# VESC1SC.net
KiCad netlist of a schematic drawn in Altium Designer
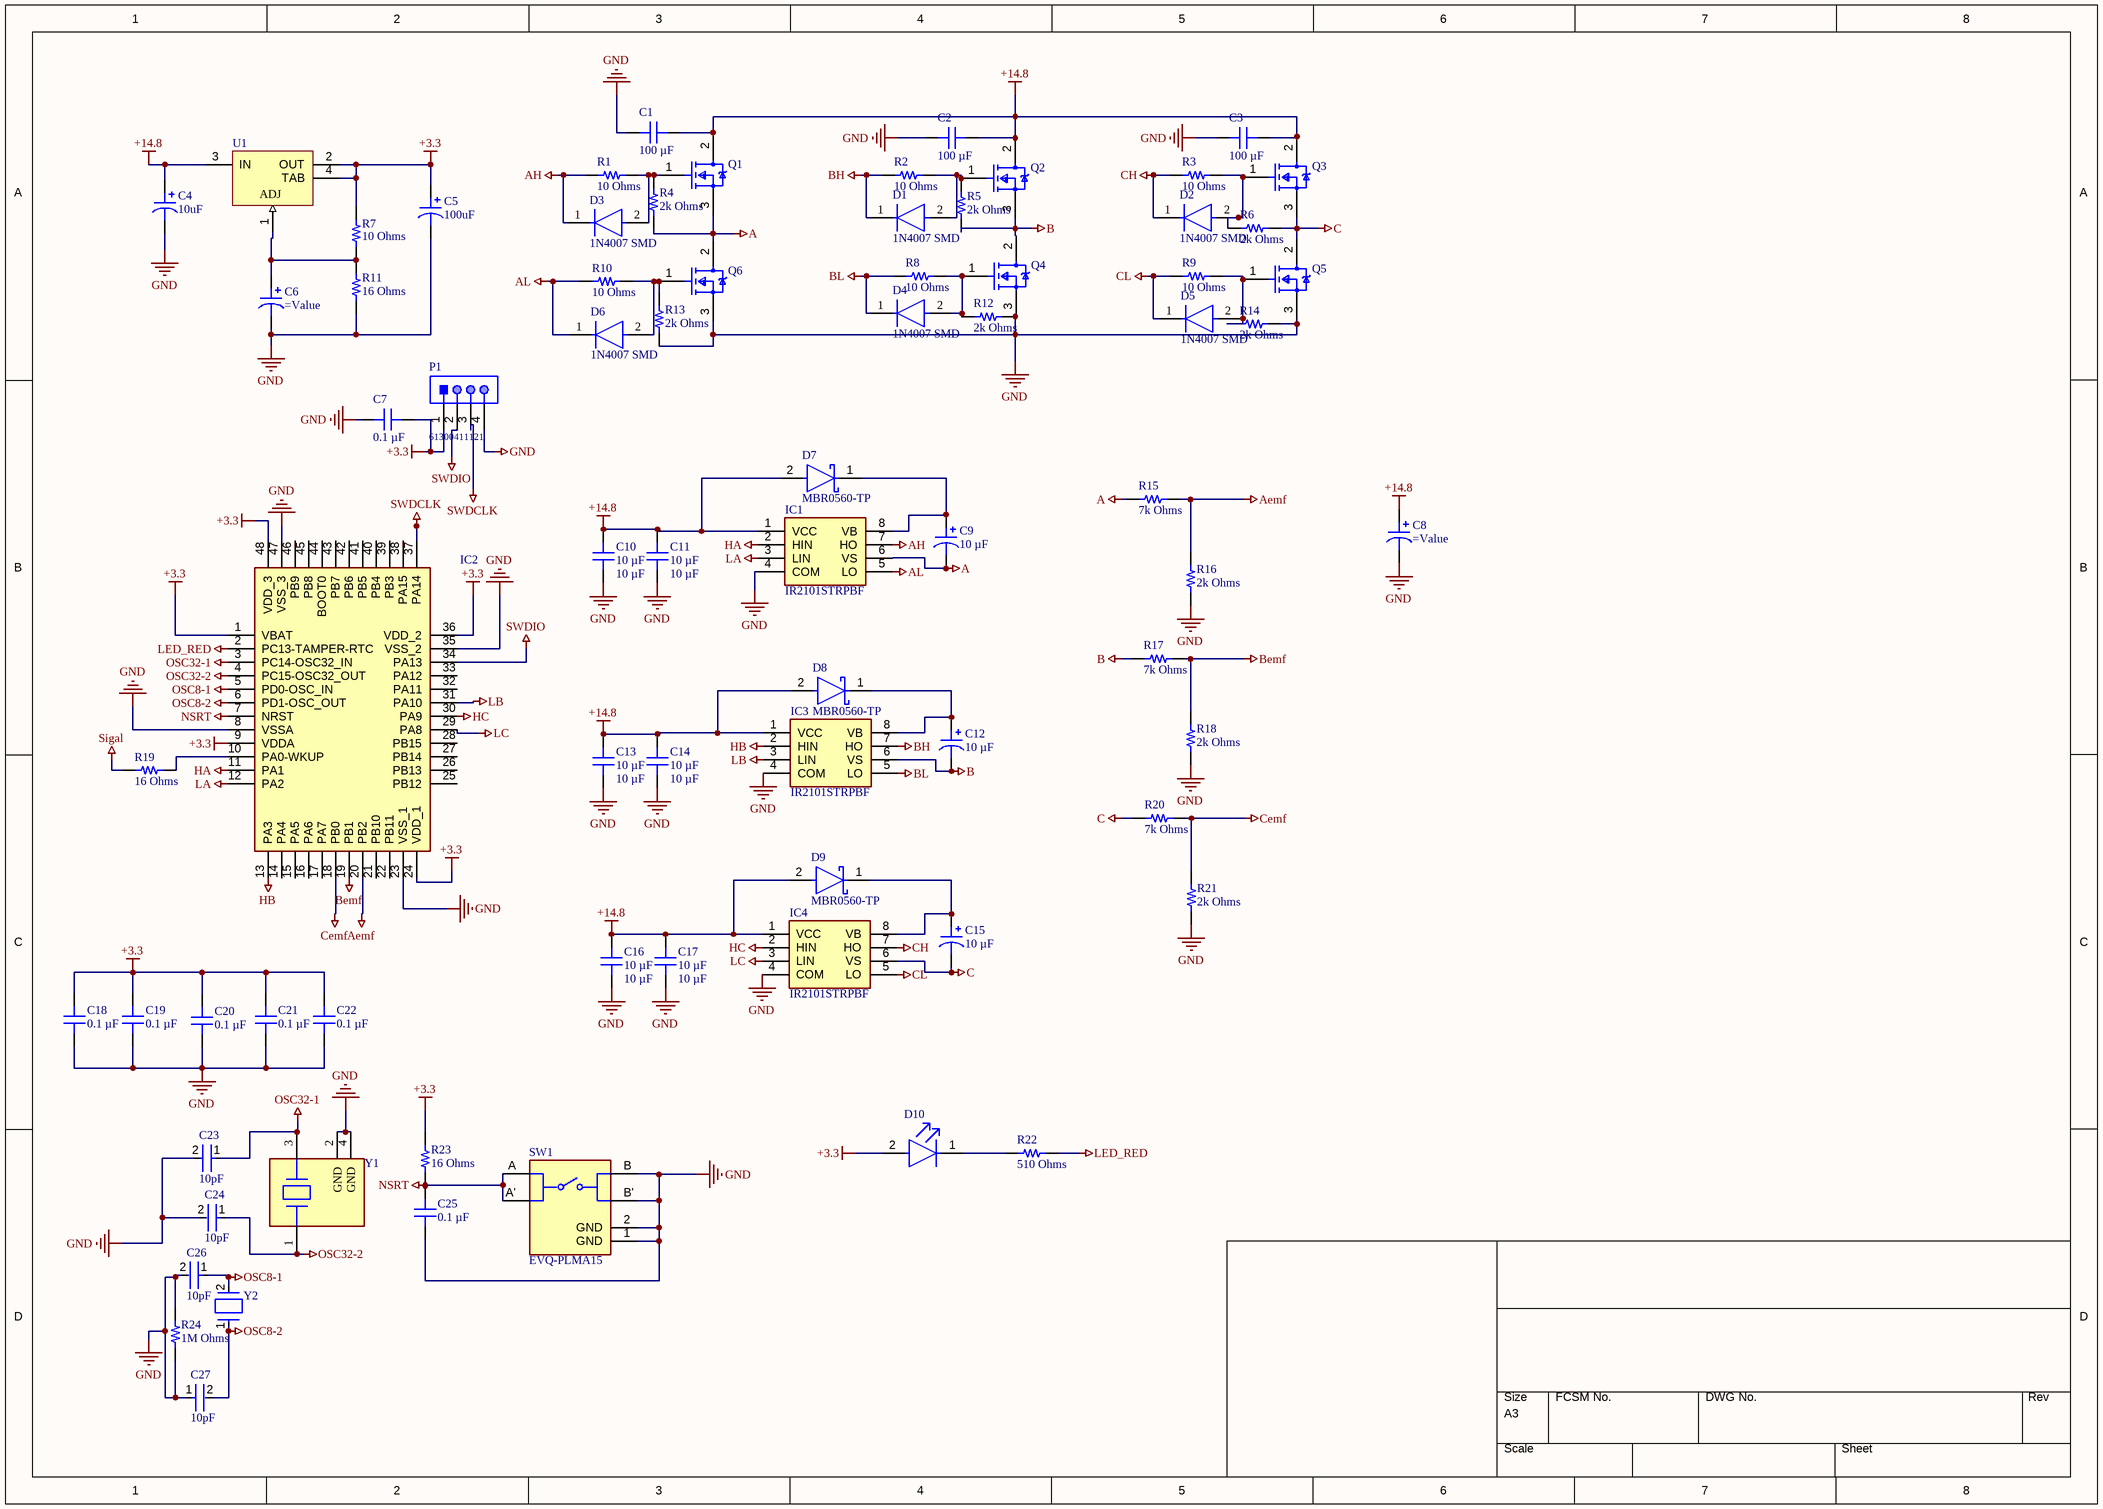
[diagram p0: VESC1SC.SchDoc]

(export (version "E")
  (design (tool "Eeschema 10.0.6"))
  (components
    (comp (ref "C1")
      (value "100 µF")
      (footprint "CAP 0805_2012")
      (description "CAP CER 100UF 2.5V X5R 0805")
      (fields (field (name "PART NUMBER") "PMK212BBJ107MG-T") (field (name "MANUFACTURER") "Taiyo Yuden"))
      (libsource (lib "Celestial Altium Library - altium_library") (part "Capacitor"))
    )
    (comp (ref "C2")
      (value "100 µF")
      (footprint "CAP 0805_2012")
      (description "CAP CER 100UF 2.5V X5R 0805")
      (fields (field (name "PART NUMBER") "PMK212BBJ107MG-T") (field (name "MANUFACTURER") "Taiyo Yuden"))
      (libsource (lib "Celestial Altium Library - altium_library") (part "Capacitor"))
    )
    (comp (ref "C3")
      (value "100 µF")
      (footprint "CAP 0805_2012")
      (description "CAP CER 100UF 2.5V X5R 0805")
      (fields (field (name "PART NUMBER") "PMK212BBJ107MG-T") (field (name "MANUFACTURER") "Taiyo Yuden"))
      (libsource (lib "Celestial Altium Library - altium_library") (part "Capacitor"))
    )
    (comp (ref "C4")
      (value "10uF")
      (footprint "CAP ALSMD 4.3MM H5.4MM")
      (description "CAP ALUM 10UF 20% 16V SMD")
      (fields (field (name "PART NUMBER") "UWX1C100MCL1GB"))
      (libsource (lib "Celestial Altium Library - altium_library") (part "Polarised Capacitor"))
    )
    (comp (ref "C5")
      (value "100uF")
      (footprint "CAP ALSMD 4.3MM H5.4MM")
      (description "CAP ALUM 10UF 20% 16V SMD")
      (fields (field (name "PART NUMBER") "UWX1C100MCL1GB"))
      (libsource (lib "Celestial Altium Library - altium_library") (part "Polarised Capacitor"))
    )
    (comp (ref "C6")
      (value "~")
      (footprint "CAP ALSMD 4.3MM H5.4MM")
      (description "CAP ALUM 10UF 20% 16V SMD")
      (fields (field (name "PART NUMBER") "UWX1C100MCL1GB"))
      (libsource (lib "Celestial Altium Library - altium_library") (part "Polarised Capacitor"))
    )
    (comp (ref "C7")
      (value "0.1 µF")
      (footprint "CAP 0805_2012")
      (description "CAP CER 0.1UF 100V X5R 0805")
      (fields (field (name "PART NUMBER") "HMK212BJ104KG-T") (field (name "MANUFACTURER") "Taiyo Yuden"))
      (libsource (lib "Celestial Altium Library - altium_library") (part "Capacitor"))
    )
    (comp (ref "C8")
      (value "~")
      (footprint "CAP TH ALUM ELEC D5.00mm S2.50mm H12.00mm")
      (description "CAP ALUM 10UF 20% 50V RADIAL")
      (fields (field (name "PART NUMBER") "ECA-1HHG100I"))
      (libsource (lib "Celestial Altium Library - altium_library") (part "Polarised Capacitor"))
    )
    (comp (ref "C9")
      (value "10 µF")
      (footprint "CAP ALSMD 4.3MM H5.4MM")
      (description "CAP ALUM 10UF 20% 16V SMD")
      (fields (field (name "PART NUMBER") "UWX1C100MCL1GB") (field (name "MANUFACTURER") "Nichicon"))
      (libsource (lib "Celestial Altium Library - altium_library") (part "Polarised Capacitor"))
    )
    (comp (ref "C10")
      (value "10 µF")
      (footprint "CAP 0805_2012")
      (description "CAP CER 10UF 16V X6S 0805")
      (fields (field (name "PART NUMBER") "C2012X6S1C106K125AC") (field (name "ALTIUM_VALUE") "10 µF"))
      (libsource (lib "Celestial Altium Library - altium_library") (part "Capacitor"))
    )
    (comp (ref "C11")
      (value "10 µF")
      (footprint "CAP 0805_2012")
      (description "CAP CER 10UF 16V X6S 0805")
      (fields (field (name "PART NUMBER") "C2012X6S1C106K125AC") (field (name "ALTIUM_VALUE") "10 µF"))
      (libsource (lib "Celestial Altium Library - altium_library") (part "Capacitor"))
    )
    (comp (ref "C12")
      (value "10 µF")
      (footprint "CAP ALSMD 4.3MM H5.4MM")
      (description "CAP ALUM 10UF 20% 16V SMD")
      (fields (field (name "PART NUMBER") "UWX1C100MCL1GB") (field (name "MANUFACTURER") "Nichicon"))
      (libsource (lib "Celestial Altium Library - altium_library") (part "Polarised Capacitor"))
    )
    (comp (ref "C13")
      (value "10 µF")
      (footprint "CAP 0805_2012")
      (description "CAP CER 10UF 16V X6S 0805")
      (fields (field (name "PART NUMBER") "C2012X6S1C106K125AC") (field (name "ALTIUM_VALUE") "10 µF"))
      (libsource (lib "Celestial Altium Library - altium_library") (part "Capacitor"))
    )
    (comp (ref "C14")
      (value "10 µF")
      (footprint "CAP 0805_2012")
      (description "CAP CER 10UF 16V X6S 0805")
      (fields (field (name "PART NUMBER") "C2012X6S1C106K125AC") (field (name "ALTIUM_VALUE") "10 µF"))
      (libsource (lib "Celestial Altium Library - altium_library") (part "Capacitor"))
    )
    (comp (ref "C15")
      (value "10 µF")
      (footprint "CAP ALSMD 4.3MM H5.4MM")
      (description "CAP ALUM 10UF 20% 16V SMD")
      (fields (field (name "PART NUMBER") "UWX1C100MCL1GB") (field (name "MANUFACTURER") "Nichicon"))
      (libsource (lib "Celestial Altium Library - altium_library") (part "Polarised Capacitor"))
    )
    (comp (ref "C16")
      (value "10 µF")
      (footprint "CAP 0805_2012")
      (description "CAP CER 10UF 16V X6S 0805")
      (fields (field (name "PART NUMBER") "C2012X6S1C106K125AC") (field (name "ALTIUM_VALUE") "10 µF"))
      (libsource (lib "Celestial Altium Library - altium_library") (part "Capacitor"))
    )
    (comp (ref "C17")
      (value "10 µF")
      (footprint "CAP 0805_2012")
      (description "CAP CER 10UF 16V X6S 0805")
      (fields (field (name "PART NUMBER") "C2012X6S1C106K125AC") (field (name "ALTIUM_VALUE") "10 µF"))
      (libsource (lib "Celestial Altium Library - altium_library") (part "Capacitor"))
    )
    (comp (ref "C18")
      (value "0.1 µF")
      (footprint "CAP 0805_2012")
      (description "CAP CER 0.1UF 100V X5R 0805")
      (fields (field (name "PART NUMBER") "HMK212BJ104KG-T") (field (name "MANUFACTURER") "Taiyo Yuden"))
      (libsource (lib "Celestial Altium Library - altium_library") (part "Capacitor"))
    )
    (comp (ref "C19")
      (value "0.1 µF")
      (footprint "CAP 0805_2012")
      (description "CAP CER 0.1UF 100V X5R 0805")
      (fields (field (name "PART NUMBER") "HMK212BJ104KG-T") (field (name "MANUFACTURER") "Taiyo Yuden"))
      (libsource (lib "Celestial Altium Library - altium_library") (part "Capacitor"))
    )
    (comp (ref "C20")
      (value "0.1 µF")
      (footprint "CAP 0805_2012")
      (description "CAP CER 0.1UF 100V X5R 0805")
      (fields (field (name "PART NUMBER") "HMK212BJ104KG-T") (field (name "MANUFACTURER") "Taiyo Yuden"))
      (libsource (lib "Celestial Altium Library - altium_library") (part "Capacitor"))
    )
    (comp (ref "C21")
      (value "0.1 µF")
      (footprint "CAP 0805_2012")
      (description "CAP CER 0.1UF 100V X5R 0805")
      (fields (field (name "PART NUMBER") "HMK212BJ104KG-T") (field (name "MANUFACTURER") "Taiyo Yuden"))
      (libsource (lib "Celestial Altium Library - altium_library") (part "Capacitor"))
    )
    (comp (ref "C22")
      (value "0.1 µF")
      (footprint "CAP 0805_2012")
      (description "CAP CER 0.1UF 100V X5R 0805")
      (fields (field (name "PART NUMBER") "HMK212BJ104KG-T") (field (name "MANUFACTURER") "Taiyo Yuden"))
      (libsource (lib "Celestial Altium Library - altium_library") (part "Capacitor"))
    )
    (comp (ref "C23")
      (value "10pF")
      (footprint "FP-C0805C-DN-MFG")
      (description "Capacitor; Ceramic; Cap 10 pF; Tol 5%; Vol-Rtg 50 VDC; SMT; 0805; COG (NPO); Tape&Reel")
      (fields
        (field (name "OCTOPART") "https://octopart.com/c0805c100j5gactu-kemet-104357")
        (field (name "MANUFACTURER PART NUMBER") "C0805C100J5GACTU")
      )
      (libsource (lib "Altium Content Vault") (part "b4654b650e69147ec39a6b967a45e02"))
    )
    (comp (ref "C24")
      (value "10pF")
      (footprint "FP-C0805C-DN-MFG")
      (description "Capacitor; Ceramic; Cap 10 pF; Tol 5%; Vol-Rtg 50 VDC; SMT; 0805; COG (NPO); Tape&Reel")
      (fields
        (field (name "OCTOPART") "https://octopart.com/c0805c100j5gactu-kemet-104357")
        (field (name "MANUFACTURER PART NUMBER") "C0805C100J5GACTU")
      )
      (libsource (lib "Altium Content Vault") (part "b4654b650e69147ec39a6b967a45e02"))
    )
    (comp (ref "C25")
      (value "0.1 µF")
      (footprint "CAP 0805_2012")
      (description "CAP CER 0.1UF 100V X5R 0805")
      (fields (field (name "PART NUMBER") "HMK212BJ104KG-T") (field (name "MANUFACTURER") "Taiyo Yuden"))
      (libsource (lib "Celestial Altium Library - altium_library") (part "Capacitor"))
    )
    (comp (ref "C26")
      (value "10pF")
      (footprint "FP-C0805C-DN-MFG")
      (description "Capacitor; Ceramic; Cap 10 pF; Tol 5%; Vol-Rtg 50 VDC; SMT; 0805; COG (NPO); Tape&Reel")
      (fields
        (field (name "OCTOPART") "https://octopart.com/c0805c100j5gactu-kemet-104357")
        (field (name "MANUFACTURER PART NUMBER") "C0805C100J5GACTU")
      )
      (libsource (lib "Altium Content Vault") (part "b4654b650e69147ec39a6b967a45e02"))
    )
    (comp (ref "C27")
      (value "10pF")
      (footprint "FP-C0805C-DN-MFG")
      (description "Capacitor; Ceramic; Cap 10 pF; Tol 5%; Vol-Rtg 50 VDC; SMT; 0805; COG (NPO); Tape&Reel")
      (fields
        (field (name "OCTOPART") "https://octopart.com/c0805c100j5gactu-kemet-104357")
        (field (name "MANUFACTURER PART NUMBER") "C0805C100J5GACTU")
      )
      (libsource (lib "Altium Content Vault") (part "b4654b650e69147ec39a6b967a45e02"))
    )
    (comp (ref "D1")
      (value "1N4007 SMD")
      (footprint "FP-1N4007_SMD-IPC_C")
      (description "Rectifier, 1Kv, 1A, Do-214Ac Rohs Compliant: Yes")
      (libsource (lib "Altium Content Vault") (part "d7152d700b627762746794eb795d46e"))
    )
    (comp (ref "D2")
      (value "1N4007 SMD")
      (footprint "FP-1N4007_SMD-IPC_C")
      (description "Rectifier, 1Kv, 1A, Do-214Ac Rohs Compliant: Yes")
      (libsource (lib "Altium Content Vault") (part "d7152d700b627762746794eb795d46e"))
    )
    (comp (ref "D3")
      (value "1N4007 SMD")
      (footprint "FP-1N4007_SMD-IPC_C")
      (description "Rectifier, 1Kv, 1A, Do-214Ac Rohs Compliant: Yes")
      (libsource (lib "Altium Content Vault") (part "d7152d700b627762746794eb795d46e"))
    )
    (comp (ref "D4")
      (value "1N4007 SMD")
      (footprint "FP-1N4007_SMD-IPC_C")
      (description "Rectifier, 1Kv, 1A, Do-214Ac Rohs Compliant: Yes")
      (libsource (lib "Altium Content Vault") (part "d7152d700b627762746794eb795d46e"))
    )
    (comp (ref "D5")
      (value "1N4007 SMD")
      (footprint "FP-1N4007_SMD-IPC_C")
      (description "Rectifier, 1Kv, 1A, Do-214Ac Rohs Compliant: Yes")
      (libsource (lib "Altium Content Vault") (part "d7152d700b627762746794eb795d46e"))
    )
    (comp (ref "D6")
      (value "1N4007 SMD")
      (footprint "FP-1N4007_SMD-IPC_C")
      (description "Rectifier, 1Kv, 1A, Do-214Ac Rohs Compliant: Yes")
      (libsource (lib "Altium Content Vault") (part "d7152d700b627762746794eb795d46e"))
    )
    (comp (ref "D7")
      (value "MBR0560-TP")
      (footprint "FP-SOD-123-IPC_C")
      (description "DIODE SCHOTTKY 60V 500MA SOD123")
      (libsource (lib "Altium Content Vault") (part "1d6ec82d83fb6aee721767c19dac4b9"))
    )
    (comp (ref "D8")
      (value "MBR0560-TP")
      (footprint "FP-SOD-123-IPC_C")
      (description "DIODE SCHOTTKY 60V 500MA SOD123")
      (libsource (lib "Altium Content Vault") (part "1d6ec82d83fb6aee721767c19dac4b9"))
    )
    (comp (ref "D9")
      (value "MBR0560-TP")
      (footprint "FP-SOD-123-IPC_C")
      (description "DIODE SCHOTTKY 60V 500MA SOD123")
      (libsource (lib "Altium Content Vault") (part "1d6ec82d83fb6aee721767c19dac4b9"))
    )
    (comp (ref "D10")
      (value "CMD15-21VRD/TR8")
      (footprint "FP-CMD15-21-MFG")
      (description "LED RED DIFFUSED 1206 SMD")
      (fields
        (field (name "MANUFACTURER") "VCC")
        (field (name "OCTOPART") "https://octopart.com/cmd15-21vrd%2Ftr8-vcc-26668835")
      )
      (libsource (lib "Altium Content Vault") (part "8706943c75ba83719d021d2fdc84c58"))
    )
    (comp (ref "IC1")
      (value "IR2101STRPBF")
      (footprint "SamacSys:SOIC127P600X175-8N")
      (description "Integrated Circuit")
      (fields (field (name "MOUSER PART NUMBER") "942-IR2101STRPBF"))
      (libsource (lib "*") (part "IR2101STRPBF"))
    )
    (comp (ref "IC2")
      (value "STM32F103C8T7")
      (footprint "SamacSys:QFP50P900X900X160-48N")
      (description "Integrated Circuit")
      (fields (field (name "MOUSER PART NUMBER") "511-STM32F103C8T7"))
      (libsource (lib "*") (part "STM32F103C8T7"))
    )
    (comp (ref "IC3")
      (value "IR2101STRPBF")
      (footprint "SamacSys:SOIC127P600X175-8N")
      (description "Integrated Circuit")
      (fields (field (name "MOUSER PART NUMBER") "942-IR2101STRPBF"))
      (libsource (lib "*") (part "IR2101STRPBF"))
    )
    (comp (ref "IC4")
      (value "IR2101STRPBF")
      (footprint "SamacSys:SOIC127P600X175-8N")
      (description "Integrated Circuit")
      (fields (field (name "MOUSER PART NUMBER") "942-IR2101STRPBF"))
      (libsource (lib "*") (part "IR2101STRPBF"))
    )
    (comp (ref "P1")
      (value "61300411121")
      (footprint "61300411121")
      (description "THT Vertical Pin Header WR-PHD, Pitch 2.54 mm, Single Row, 4 pins")
      (fields (field (name "MANUFACTURER") "Wurth Elektronik") (field (name "PUBLISHER") "WurthElektronik"))
      (libsource (lib "Altium Content Vault") (part "WE-CN-1P-M-R4"))
    )
    (comp (ref "Q1")
      (value "IRF3205STRLPBF")
      (footprint "FP-PG-TO263-3-MFG")
      (description "MOSFET N-CH 55V 110A D2PAK")
      (fields
        (field (name "MANUFACTURER") "Infineon Technologies")
        (field (name "OCTOPART") "https://octopart.com/irf3205strlpbf-infineon-65873335")
      )
      (libsource (lib "Altium Content Vault") (part "b09f7f152735e370c1ea22a33fa83d6"))
    )
    (comp (ref "Q2")
      (value "IRF3205STRLPBF")
      (footprint "FP-PG-TO263-3-MFG")
      (description "MOSFET N-CH 55V 110A D2PAK")
      (fields
        (field (name "MANUFACTURER") "Infineon Technologies")
        (field (name "OCTOPART") "https://octopart.com/irf3205strlpbf-infineon-65873335")
      )
      (libsource (lib "Altium Content Vault") (part "b09f7f152735e370c1ea22a33fa83d6"))
    )
    (comp (ref "Q3")
      (value "IRF3205STRLPBF")
      (footprint "FP-PG-TO263-3-MFG")
      (description "MOSFET N-CH 55V 110A D2PAK")
      (fields
        (field (name "MANUFACTURER") "Infineon Technologies")
        (field (name "OCTOPART") "https://octopart.com/irf3205strlpbf-infineon-65873335")
      )
      (libsource (lib "Altium Content Vault") (part "b09f7f152735e370c1ea22a33fa83d6"))
    )
    (comp (ref "Q4")
      (value "IRF3205STRLPBF")
      (footprint "FP-PG-TO263-3-MFG")
      (description "MOSFET N-CH 55V 110A D2PAK")
      (fields
        (field (name "MANUFACTURER") "Infineon Technologies")
        (field (name "OCTOPART") "https://octopart.com/irf3205strlpbf-infineon-65873335")
      )
      (libsource (lib "Altium Content Vault") (part "b09f7f152735e370c1ea22a33fa83d6"))
    )
    (comp (ref "Q5")
      (value "IRF3205STRLPBF")
      (footprint "FP-PG-TO263-3-MFG")
      (description "MOSFET N-CH 55V 110A D2PAK")
      (fields
        (field (name "MANUFACTURER") "Infineon Technologies")
        (field (name "OCTOPART") "https://octopart.com/irf3205strlpbf-infineon-65873335")
      )
      (libsource (lib "Altium Content Vault") (part "b09f7f152735e370c1ea22a33fa83d6"))
    )
    (comp (ref "Q6")
      (value "IRF3205STRLPBF")
      (footprint "FP-PG-TO263-3-MFG")
      (description "MOSFET N-CH 55V 110A D2PAK")
      (fields
        (field (name "MANUFACTURER") "Infineon Technologies")
        (field (name "OCTOPART") "https://octopart.com/irf3205strlpbf-infineon-65873335")
      )
      (libsource (lib "Altium Content Vault") (part "b09f7f152735e370c1ea22a33fa83d6"))
    )
    (comp (ref "R1")
      (value "10 Ohms")
      (footprint "RES 0603_1608")
      (description "RES 10K OHM 0.1% 1/16W 0603")
      (fields
        (field (name "PART NUMBER") "RNCS0603BKE10K0")
        (field (name "MANUFACTURER") "Stackpole Electronics Inc")
      )
      (libsource (lib "Celestial Altium Library - altium_library") (part "Resistor"))
    )
    (comp (ref "R2")
      (value "10 Ohms")
      (footprint "RES 0603_1608")
      (description "RES 10K OHM 0.1% 1/16W 0603")
      (fields
        (field (name "PART NUMBER") "RNCS0603BKE10K0")
        (field (name "MANUFACTURER") "Stackpole Electronics Inc")
      )
      (libsource (lib "Celestial Altium Library - altium_library") (part "Resistor"))
    )
    (comp (ref "R3")
      (value "10 Ohms")
      (footprint "RES 0603_1608")
      (description "RES 10K OHM 0.1% 1/16W 0603")
      (fields
        (field (name "PART NUMBER") "RNCS0603BKE10K0")
        (field (name "MANUFACTURER") "Stackpole Electronics Inc")
      )
      (libsource (lib "Celestial Altium Library - altium_library") (part "Resistor"))
    )
    (comp (ref "R4")
      (value "2k Ohms")
      (footprint "RES 0603_1608")
      (description "RES 10K OHM 0.1% 1/16W 0603")
      (fields
        (field (name "PART NUMBER") "RNCS0603BKE10K0")
        (field (name "MANUFACTURER") "Stackpole Electronics Inc")
      )
      (libsource (lib "Celestial Altium Library - altium_library") (part "Resistor"))
    )
    (comp (ref "R5")
      (value "2k Ohms")
      (footprint "RES 0603_1608")
      (description "RES 10K OHM 0.1% 1/16W 0603")
      (fields
        (field (name "PART NUMBER") "RNCS0603BKE10K0")
        (field (name "MANUFACTURER") "Stackpole Electronics Inc")
      )
      (libsource (lib "Celestial Altium Library - altium_library") (part "Resistor"))
    )
    (comp (ref "R6")
      (value "2k Ohms")
      (footprint "RES 0603_1608")
      (description "RES 10K OHM 0.1% 1/16W 0603")
      (fields
        (field (name "PART NUMBER") "RNCS0603BKE10K0")
        (field (name "MANUFACTURER") "Stackpole Electronics Inc")
      )
      (libsource (lib "Celestial Altium Library - altium_library") (part "Resistor"))
    )
    (comp (ref "R7")
      (value "10 Ohms")
      (footprint "RES 0603_1608")
      (description "RES 10K OHM 0.1% 1/16W 0603")
      (fields
        (field (name "PART NUMBER") "RNCS0603BKE10K0")
        (field (name "MANUFACTURER") "Stackpole Electronics Inc")
      )
      (libsource (lib "Celestial Altium Library - altium_library") (part "Resistor"))
    )
    (comp (ref "R8")
      (value "10 Ohms")
      (footprint "RES 0603_1608")
      (description "RES 10K OHM 0.1% 1/16W 0603")
      (fields
        (field (name "PART NUMBER") "RNCS0603BKE10K0")
        (field (name "MANUFACTURER") "Stackpole Electronics Inc")
      )
      (libsource (lib "Celestial Altium Library - altium_library") (part "Resistor"))
    )
    (comp (ref "R9")
      (value "10 Ohms")
      (footprint "RES 0603_1608")
      (description "RES 10K OHM 0.1% 1/16W 0603")
      (fields
        (field (name "PART NUMBER") "RNCS0603BKE10K0")
        (field (name "MANUFACTURER") "Stackpole Electronics Inc")
      )
      (libsource (lib "Celestial Altium Library - altium_library") (part "Resistor"))
    )
    (comp (ref "R10")
      (value "10 Ohms")
      (footprint "RES 0603_1608")
      (description "RES 10K OHM 0.1% 1/16W 0603")
      (fields
        (field (name "PART NUMBER") "RNCS0603BKE10K0")
        (field (name "MANUFACTURER") "Stackpole Electronics Inc")
      )
      (libsource (lib "Celestial Altium Library - altium_library") (part "Resistor"))
    )
    (comp (ref "R11")
      (value "16 Ohms")
      (footprint "RES 0603_1608")
      (description "RES 10K OHM 0.1% 1/16W 0603")
      (fields
        (field (name "PART NUMBER") "RNCS0603BKE10K0")
        (field (name "MANUFACTURER") "Stackpole Electronics Inc")
      )
      (libsource (lib "Celestial Altium Library - altium_library") (part "Resistor"))
    )
    (comp (ref "R12")
      (value "2k Ohms")
      (footprint "RES 0603_1608")
      (description "RES 10K OHM 0.1% 1/16W 0603")
      (fields
        (field (name "PART NUMBER") "RNCS0603BKE10K0")
        (field (name "MANUFACTURER") "Stackpole Electronics Inc")
      )
      (libsource (lib "Celestial Altium Library - altium_library") (part "Resistor"))
    )
    (comp (ref "R13")
      (value "2k Ohms")
      (footprint "RES 0603_1608")
      (description "RES 10K OHM 0.1% 1/16W 0603")
      (fields
        (field (name "PART NUMBER") "RNCS0603BKE10K0")
        (field (name "MANUFACTURER") "Stackpole Electronics Inc")
      )
      (libsource (lib "Celestial Altium Library - altium_library") (part "Resistor"))
    )
    (comp (ref "R14")
      (value "2k Ohms")
      (footprint "RES 0603_1608")
      (description "RES 10K OHM 0.1% 1/16W 0603")
      (fields
        (field (name "PART NUMBER") "RNCS0603BKE10K0")
        (field (name "MANUFACTURER") "Stackpole Electronics Inc")
      )
      (libsource (lib "Celestial Altium Library - altium_library") (part "Resistor"))
    )
    (comp (ref "R15")
      (value "7k Ohms")
      (footprint "RES 0603_1608")
      (description "RES 10K OHM 0.1% 1/16W 0603")
      (fields
        (field (name "PART NUMBER") "RNCS0603BKE10K0")
        (field (name "MANUFACTURER") "Stackpole Electronics Inc")
      )
      (libsource (lib "Celestial Altium Library - altium_library") (part "Resistor"))
    )
    (comp (ref "R16")
      (value "2k Ohms")
      (footprint "RES 0603_1608")
      (description "RES 10K OHM 0.1% 1/16W 0603")
      (fields
        (field (name "PART NUMBER") "RNCS0603BKE10K0")
        (field (name "MANUFACTURER") "Stackpole Electronics Inc")
      )
      (libsource (lib "Celestial Altium Library - altium_library") (part "Resistor"))
    )
    (comp (ref "R17")
      (value "7k Ohms")
      (footprint "RES 0603_1608")
      (description "RES 10K OHM 0.1% 1/16W 0603")
      (fields
        (field (name "PART NUMBER") "RNCS0603BKE10K0")
        (field (name "MANUFACTURER") "Stackpole Electronics Inc")
      )
      (libsource (lib "Celestial Altium Library - altium_library") (part "Resistor"))
    )
    (comp (ref "R18")
      (value "2k Ohms")
      (footprint "RES 0603_1608")
      (description "RES 10K OHM 0.1% 1/16W 0603")
      (fields
        (field (name "PART NUMBER") "RNCS0603BKE10K0")
        (field (name "MANUFACTURER") "Stackpole Electronics Inc")
      )
      (libsource (lib "Celestial Altium Library - altium_library") (part "Resistor"))
    )
    (comp (ref "R19")
      (value "16 Ohms")
      (footprint "RES 0603_1608")
      (description "RES 10K OHM 0.1% 1/16W 0603")
      (fields
        (field (name "PART NUMBER") "RNCS0603BKE10K0")
        (field (name "MANUFACTURER") "Stackpole Electronics Inc")
      )
      (libsource (lib "Celestial Altium Library - altium_library") (part "Resistor"))
    )
    (comp (ref "R20")
      (value "7k Ohms")
      (footprint "RES 0603_1608")
      (description "RES 10K OHM 0.1% 1/16W 0603")
      (fields
        (field (name "PART NUMBER") "RNCS0603BKE10K0")
        (field (name "MANUFACTURER") "Stackpole Electronics Inc")
      )
      (libsource (lib "Celestial Altium Library - altium_library") (part "Resistor"))
    )
    (comp (ref "R21")
      (value "2k Ohms")
      (footprint "RES 0603_1608")
      (description "RES 10K OHM 0.1% 1/16W 0603")
      (fields
        (field (name "PART NUMBER") "RNCS0603BKE10K0")
        (field (name "MANUFACTURER") "Stackpole Electronics Inc")
      )
      (libsource (lib "Celestial Altium Library - altium_library") (part "Resistor"))
    )
    (comp (ref "R22")
      (value "510 Ohms")
      (footprint "RES 0603_1608")
      (description "RES 10K OHM 0.1% 1/16W 0603")
      (fields
        (field (name "PART NUMBER") "RNCS0603BKE10K0")
        (field (name "MANUFACTURER") "Stackpole Electronics Inc")
      )
      (libsource (lib "Celestial Altium Library - altium_library") (part "Resistor"))
    )
    (comp (ref "R23")
      (value "16 Ohms")
      (footprint "RES 0603_1608")
      (description "RES 10K OHM 0.1% 1/16W 0603")
      (fields
        (field (name "PART NUMBER") "RNCS0603BKE10K0")
        (field (name "MANUFACTURER") "Stackpole Electronics Inc")
      )
      (libsource (lib "Celestial Altium Library - altium_library") (part "Resistor"))
    )
    (comp (ref "R24")
      (value "1M Ohms")
      (footprint "RES 0603_1608")
      (description "RES 10K OHM 0.1% 1/16W 0603")
      (fields
        (field (name "PART NUMBER") "RNCS0603BKE10K0")
        (field (name "MANUFACTURER") "Stackpole Electronics Inc")
      )
      (libsource (lib "Celestial Altium Library - altium_library") (part "Resistor"))
    )
    (comp (ref "SW1")
      (value "EVQ-PLMA15")
      (footprint "FP-EVQ-PLMA15-MFG")
      (description "SWITCH TACTILE SPST-NO 0.02A 15V")
      (fields
        (field (name "OCTOPART") "https://octopart.com/evq-plma15-panasonic-39850235")
        (field (name "MANUFACTURER") "Panasonic Electronic Components")
      )
      (libsource (lib "Altium Content Vault") (part "fc7b47d2e4813f0909612a6c4f63938"))
    )
    (comp (ref "U1")
      (value "LM1117MPX-ADJ/NOPB")
      (footprint "DCY0004A_N")
      (description "800mA Low-Dropout Linear Regulator, 4-pin SOT-223, Pb-Free")
      (fields (field (name "MANUFACTURER") "Texas Instruments"))
      (libsource (lib "Altium Content Vault") (part "PM-REG-LM1086ADJ-SOT4"))
    )
    (comp (ref "Y1")
      (value "ABM3B-155-12.800MHZ-T")
      (footprint "FP-ABM3B-MFG")
      (description "Crystal 12.8MHz ±10ppm 15pF SMD-4 5mm x 3.2mm")
      (fields (field (name "TOLERANCE") "50ppm"))
      (libsource (lib "Altium Content Vault") (part "48e526d86b7f2615d98721063c72f49"))
    )
    (comp (ref "Y2")
      (value "ABM3-8.000MHZ-D2Y-T")
      (footprint "FP-ABM3-MFG")
      (description "Crystal 8MHz ±20ppm 18pF SMD-2 5mm x 3.2mm")
      (fields (field (name "TOLERANCE") "20ppm"))
      (libsource (lib "Altium Content Vault") (part "c23a69dc6c9e2f18f2079038eb95dd1"))
    )
  )
  (nets
    (net (code "1") (name "+3.3") (class "Default")
      (node (ref "C18") (pin "2") (pinfunction "2_2") (pintype "passive"))
      (node (ref "C19") (pin "2") (pinfunction "2_2") (pintype "passive"))
      (node (ref "C20") (pin "2") (pinfunction "2_2") (pintype "passive"))
      (node (ref "C21") (pin "2") (pinfunction "2_2") (pintype "passive"))
      (node (ref "C22") (pin "2") (pinfunction "2_2") (pintype "passive"))
      (node (ref "C5") (pin "1") (pinfunction "1_1") (pintype "passive"))
      (node (ref "C7") (pin "1") (pinfunction "1_1") (pintype "passive"))
      (node (ref "D10") (pin "2") (pinfunction "A_2") (pintype "passive"))
      (node (ref "IC2") (pin "1") (pinfunction "VBAT_1") (pintype "passive"))
      (node (ref "IC2") (pin "24") (pinfunction "VDD_1_24") (pintype "passive"))
      (node (ref "IC2") (pin "36") (pinfunction "VDD_2_36") (pintype "passive"))
      (node (ref "IC2") (pin "48") (pinfunction "VDD_3_48") (pintype "passive"))
      (node (ref "IC2") (pin "9") (pinfunction "VDDA_9") (pintype "passive"))
      (node (ref "P1") (pin "1") (pinfunction "1_1") (pintype "passive"))
      (node (ref "R23") (pin "1") (pinfunction "1_1") (pintype "passive"))
      (node (ref "R7") (pin "2") (pinfunction "2_2") (pintype "passive"))
      (node (ref "U1") (pin "2") (pinfunction "OUT_2") (pintype "power_in"))
      (node (ref "U1") (pin "4") (pinfunction "TAB_4") (pintype "power_in"))
    )
    (net (code "2") (name "+14.8") (class "Default")
      (node (ref "C1") (pin "1") (pinfunction "1_1") (pintype "passive"))
      (node (ref "C10") (pin "2") (pinfunction "2_2") (pintype "passive"))
      (node (ref "C11") (pin "2") (pinfunction "2_2") (pintype "passive"))
      (node (ref "C13") (pin "2") (pinfunction "2_2") (pintype "passive"))
      (node (ref "C14") (pin "2") (pinfunction "2_2") (pintype "passive"))
      (node (ref "C16") (pin "2") (pinfunction "2_2") (pintype "passive"))
      (node (ref "C17") (pin "2") (pinfunction "2_2") (pintype "passive"))
      (node (ref "C2") (pin "1") (pinfunction "1_1") (pintype "passive"))
      (node (ref "C3") (pin "1") (pinfunction "1_1") (pintype "passive"))
      (node (ref "C4") (pin "1") (pinfunction "1_1") (pintype "passive"))
      (node (ref "C8") (pin "1") (pinfunction "1_1") (pintype "passive"))
      (node (ref "D7") (pin "2") (pinfunction "A_2") (pintype "passive"))
      (node (ref "D8") (pin "2") (pinfunction "A_2") (pintype "passive"))
      (node (ref "D9") (pin "2") (pinfunction "A_2") (pintype "passive"))
      (node (ref "IC1") (pin "1") (pinfunction "VCC_1") (pintype "passive"))
      (node (ref "IC3") (pin "1") (pinfunction "VCC_1") (pintype "passive"))
      (node (ref "IC4") (pin "1") (pinfunction "VCC_1") (pintype "passive"))
      (node (ref "Q1") (pin "2") (pinfunction "D_2") (pintype "passive"))
      (node (ref "Q2") (pin "2") (pinfunction "D_2") (pintype "passive"))
      (node (ref "Q3") (pin "2") (pinfunction "D_2") (pintype "passive"))
      (node (ref "U1") (pin "3") (pinfunction "IN_3") (pintype "power_in"))
    )
    (net (code "3") (name "A") (class "Default")
      (node (ref "C9") (pin "2") (pinfunction "2_2") (pintype "passive"))
      (node (ref "IC1") (pin "6") (pinfunction "VS_6") (pintype "passive"))
      (node (ref "Q1") (pin "3") (pinfunction "S_3") (pintype "passive"))
      (node (ref "Q6") (pin "2") (pinfunction "D_2") (pintype "passive"))
      (node (ref "R15") (pin "1") (pinfunction "1_1") (pintype "passive"))
      (node (ref "R4") (pin "1") (pinfunction "1_1") (pintype "passive"))
    )
    (net (code "4") (name "AH") (class "Default")
      (node (ref "D3") (pin "1") (pinfunction "C_1") (pintype "passive"))
      (node (ref "IC1") (pin "7") (pinfunction "HO_7") (pintype "passive"))
      (node (ref "R1") (pin "1") (pinfunction "1_1") (pintype "passive"))
    )
    (net (code "5") (name "AL") (class "Default")
      (node (ref "D6") (pin "1") (pinfunction "C_1") (pintype "passive"))
      (node (ref "IC1") (pin "5") (pinfunction "LO_5") (pintype "passive"))
      (node (ref "R10") (pin "1") (pinfunction "1_1") (pintype "passive"))
    )
    (net (code "6") (name "Aemf") (class "Default")
      (node (ref "IC2") (pin "20") (pinfunction "PB2_20") (pintype "passive"))
      (node (ref "R15") (pin "2") (pinfunction "2_2") (pintype "passive"))
      (node (ref "R16") (pin "2") (pinfunction "2_2") (pintype "passive"))
    )
    (net (code "7") (name "B") (class "Default")
      (node (ref "C12") (pin "2") (pinfunction "2_2") (pintype "passive"))
      (node (ref "IC3") (pin "6") (pinfunction "VS_6") (pintype "passive"))
      (node (ref "Q2") (pin "3") (pinfunction "S_3") (pintype "passive"))
      (node (ref "Q4") (pin "2") (pinfunction "D_2") (pintype "passive"))
      (node (ref "R17") (pin "1") (pinfunction "1_1") (pintype "passive"))
      (node (ref "R5") (pin "1") (pinfunction "1_1") (pintype "passive"))
    )
    (net (code "8") (name "BH") (class "Default")
      (node (ref "D1") (pin "1") (pinfunction "C_1") (pintype "passive"))
      (node (ref "IC3") (pin "7") (pinfunction "HO_7") (pintype "passive"))
      (node (ref "R2") (pin "1") (pinfunction "1_1") (pintype "passive"))
    )
    (net (code "9") (name "BL") (class "Default")
      (node (ref "D4") (pin "1") (pinfunction "C_1") (pintype "passive"))
      (node (ref "IC3") (pin "5") (pinfunction "LO_5") (pintype "passive"))
      (node (ref "R8") (pin "1") (pinfunction "1_1") (pintype "passive"))
    )
    (net (code "10") (name "Bemf") (class "Default")
      (node (ref "IC2") (pin "19") (pinfunction "PB1_19") (pintype "passive"))
      (node (ref "R17") (pin "2") (pinfunction "2_2") (pintype "passive"))
      (node (ref "R18") (pin "2") (pinfunction "2_2") (pintype "passive"))
    )
    (net (code "11") (name "C") (class "Default")
      (node (ref "C15") (pin "2") (pinfunction "2_2") (pintype "passive"))
      (node (ref "IC4") (pin "6") (pinfunction "VS_6") (pintype "passive"))
      (node (ref "Q3") (pin "3") (pinfunction "S_3") (pintype "passive"))
      (node (ref "Q5") (pin "2") (pinfunction "D_2") (pintype "passive"))
      (node (ref "R20") (pin "1") (pinfunction "1_1") (pintype "passive"))
      (node (ref "R6") (pin "1") (pinfunction "1_1") (pintype "passive"))
    )
    (net (code "12") (name "CH") (class "Default")
      (node (ref "D2") (pin "1") (pinfunction "C_1") (pintype "passive"))
      (node (ref "IC4") (pin "7") (pinfunction "HO_7") (pintype "passive"))
      (node (ref "R3") (pin "1") (pinfunction "1_1") (pintype "passive"))
    )
    (net (code "13") (name "CL") (class "Default")
      (node (ref "D5") (pin "1") (pinfunction "C_1") (pintype "passive"))
      (node (ref "IC4") (pin "5") (pinfunction "LO_5") (pintype "passive"))
      (node (ref "R9") (pin "1") (pinfunction "1_1") (pintype "passive"))
    )
    (net (code "14") (name "Cemf") (class "Default")
      (node (ref "IC2") (pin "18") (pinfunction "PB0_18") (pintype "passive"))
      (node (ref "R20") (pin "2") (pinfunction "2_2") (pintype "passive"))
      (node (ref "R21") (pin "2") (pinfunction "2_2") (pintype "passive"))
    )
    (net (code "15") (name "GND") (class "Default")
      (node (ref "C1") (pin "2") (pinfunction "2_2") (pintype "passive"))
      (node (ref "C10") (pin "1") (pinfunction "1_1") (pintype "passive"))
      (node (ref "C11") (pin "1") (pinfunction "1_1") (pintype "passive"))
      (node (ref "C13") (pin "1") (pinfunction "1_1") (pintype "passive"))
      (node (ref "C14") (pin "1") (pinfunction "1_1") (pintype "passive"))
      (node (ref "C16") (pin "1") (pinfunction "1_1") (pintype "passive"))
      (node (ref "C17") (pin "1") (pinfunction "1_1") (pintype "passive"))
      (node (ref "C18") (pin "1") (pinfunction "1_1") (pintype "passive"))
      (node (ref "C19") (pin "1") (pinfunction "1_1") (pintype "passive"))
      (node (ref "C2") (pin "2") (pinfunction "2_2") (pintype "passive"))
      (node (ref "C20") (pin "1") (pinfunction "1_1") (pintype "passive"))
      (node (ref "C21") (pin "1") (pinfunction "1_1") (pintype "passive"))
      (node (ref "C22") (pin "1") (pinfunction "1_1") (pintype "passive"))
      (node (ref "C23") (pin "2") (pinfunction "2_2") (pintype "passive"))
      (node (ref "C24") (pin "2") (pinfunction "2_2") (pintype "passive"))
      (node (ref "C25") (pin "1") (pinfunction "1_1") (pintype "passive"))
      (node (ref "C26") (pin "2") (pinfunction "2_2") (pintype "passive"))
      (node (ref "C27") (pin "1") (pinfunction "1_1") (pintype "passive"))
      (node (ref "C3") (pin "2") (pinfunction "2_2") (pintype "passive"))
      (node (ref "C4") (pin "2") (pinfunction "2_2") (pintype "passive"))
      (node (ref "C5") (pin "2") (pinfunction "2_2") (pintype "passive"))
      (node (ref "C6") (pin "2") (pinfunction "2_2") (pintype "passive"))
      (node (ref "C7") (pin "2") (pinfunction "2_2") (pintype "passive"))
      (node (ref "C8") (pin "2") (pinfunction "2_2") (pintype "passive"))
      (node (ref "IC1") (pin "4") (pinfunction "COM_4") (pintype "passive"))
      (node (ref "IC2") (pin "23") (pinfunction "VSS_1_23") (pintype "passive"))
      (node (ref "IC2") (pin "35") (pinfunction "VSS_2_35") (pintype "passive"))
      (node (ref "IC2") (pin "47") (pinfunction "VSS_3_47") (pintype "passive"))
      (node (ref "IC2") (pin "8") (pinfunction "VSSA_8") (pintype "passive"))
      (node (ref "IC3") (pin "4") (pinfunction "COM_4") (pintype "passive"))
      (node (ref "IC4") (pin "4") (pinfunction "COM_4") (pintype "passive"))
      (node (ref "P1") (pin "4") (pinfunction "4_4") (pintype "passive"))
      (node (ref "Q4") (pin "3") (pinfunction "S_3") (pintype "passive"))
      (node (ref "Q5") (pin "3") (pinfunction "S_3") (pintype "passive"))
      (node (ref "Q6") (pin "3") (pinfunction "S_3") (pintype "passive"))
      (node (ref "R11") (pin "1") (pinfunction "1_1") (pintype "passive"))
      (node (ref "R12") (pin "1") (pinfunction "1_1") (pintype "passive"))
      (node (ref "R13") (pin "1") (pinfunction "1_1") (pintype "passive"))
      (node (ref "R14") (pin "1") (pinfunction "1_1") (pintype "passive"))
      (node (ref "R16") (pin "1") (pinfunction "1_1") (pintype "passive"))
      (node (ref "R18") (pin "1") (pinfunction "1_1") (pintype "passive"))
      (node (ref "R21") (pin "1") (pinfunction "1_1") (pintype "passive"))
      (node (ref "R24") (pin "1") (pinfunction "1_1") (pintype "passive"))
      (node (ref "R24") (pin "2") (pinfunction "2_2") (pintype "passive"))
      (node (ref "SW1") (pin "1") (pinfunction "GND_1") (pintype "power_in"))
      (node (ref "SW1") (pin "2") (pinfunction "GND_2") (pintype "power_in"))
      (node (ref "SW1") (pin "B") (pinfunction "B_B") (pintype "passive"))
      (node (ref "SW1") (pin "B'") (pinfunction "B'_B'") (pintype "passive"))
      (node (ref "Y1") (pin "2") (pinfunction "GND_2") (pintype "power_in"))
      (node (ref "Y1") (pin "4") (pinfunction "GND_4") (pintype "power_in"))
    )
    (net (code "16") (name "HA") (class "Default")
      (node (ref "IC1") (pin "2") (pinfunction "HIN_2") (pintype "passive"))
      (node (ref "IC2") (pin "11") (pinfunction "PA1_11") (pintype "passive"))
    )
    (net (code "17") (name "HB") (class "Default")
      (node (ref "IC2") (pin "13") (pinfunction "PA3_13") (pintype "passive"))
      (node (ref "IC3") (pin "2") (pinfunction "HIN_2") (pintype "passive"))
    )
    (net (code "18") (name "HC") (class "Default")
      (node (ref "IC2") (pin "30") (pinfunction "PA9_30") (pintype "passive"))
      (node (ref "IC4") (pin "2") (pinfunction "HIN_2") (pintype "passive"))
    )
    (net (code "19") (name "LA") (class "Default")
      (node (ref "IC1") (pin "3") (pinfunction "LIN_3") (pintype "passive"))
      (node (ref "IC2") (pin "12") (pinfunction "PA2_12") (pintype "passive"))
    )
    (net (code "20") (name "LB") (class "Default")
      (node (ref "IC2") (pin "31") (pinfunction "PA10_31") (pintype "passive"))
      (node (ref "IC3") (pin "3") (pinfunction "LIN_3") (pintype "passive"))
    )
    (net (code "21") (name "LC") (class "Default")
      (node (ref "IC2") (pin "29") (pinfunction "PA8_29") (pintype "passive"))
      (node (ref "IC4") (pin "3") (pinfunction "LIN_3") (pintype "passive"))
    )
    (net (code "22") (name "LED_RED") (class "Default")
      (node (ref "IC2") (pin "2") (pinfunction "PC13-TAMPER-RTC_2") (pintype "passive"))
      (node (ref "R22") (pin "2") (pinfunction "2_2") (pintype "passive"))
    )
    (net (code "23") (name "NSRT") (class "Default")
      (node (ref "C25") (pin "2") (pinfunction "2_2") (pintype "passive"))
      (node (ref "IC2") (pin "7") (pinfunction "NRST_7") (pintype "passive"))
      (node (ref "R23") (pin "2") (pinfunction "2_2") (pintype "passive"))
      (node (ref "SW1") (pin "A") (pinfunction "A_A") (pintype "passive"))
      (node (ref "SW1") (pin "A'") (pinfunction "A'_A'") (pintype "passive"))
    )
    (net (code "24") (name "Net-(D1-A)") (class "Default")
      (node (ref "D1") (pin "2") (pinfunction "A_2") (pintype "passive"))
      (node (ref "Q2") (pin "1") (pinfunction "G_1") (pintype "passive"))
      (node (ref "R2") (pin "2") (pinfunction "2_2") (pintype "passive"))
      (node (ref "R5") (pin "2") (pinfunction "2_2") (pintype "passive"))
    )
    (net (code "25") (name "Net-(D2-A)") (class "Default")
      (node (ref "D2") (pin "2") (pinfunction "A_2") (pintype "passive"))
      (node (ref "Q3") (pin "1") (pinfunction "G_1") (pintype "passive"))
      (node (ref "R3") (pin "2") (pinfunction "2_2") (pintype "passive"))
      (node (ref "R6") (pin "2") (pinfunction "2_2") (pintype "passive"))
    )
    (net (code "26") (name "Net-(D3-A)") (class "Default")
      (node (ref "D3") (pin "2") (pinfunction "A_2") (pintype "passive"))
      (node (ref "Q1") (pin "1") (pinfunction "G_1") (pintype "passive"))
      (node (ref "R1") (pin "2") (pinfunction "2_2") (pintype "passive"))
      (node (ref "R4") (pin "2") (pinfunction "2_2") (pintype "passive"))
    )
    (net (code "27") (name "Net-(D4-A)") (class "Default")
      (node (ref "D4") (pin "2") (pinfunction "A_2") (pintype "passive"))
      (node (ref "Q4") (pin "1") (pinfunction "G_1") (pintype "passive"))
      (node (ref "R12") (pin "2") (pinfunction "2_2") (pintype "passive"))
      (node (ref "R8") (pin "2") (pinfunction "2_2") (pintype "passive"))
    )
    (net (code "28") (name "Net-(D5-A)") (class "Default")
      (node (ref "D5") (pin "2") (pinfunction "A_2") (pintype "passive"))
      (node (ref "Q5") (pin "1") (pinfunction "G_1") (pintype "passive"))
      (node (ref "R14") (pin "2") (pinfunction "2_2") (pintype "passive"))
      (node (ref "R9") (pin "2") (pinfunction "2_2") (pintype "passive"))
    )
    (net (code "29") (name "Net-(D6-A)") (class "Default")
      (node (ref "D6") (pin "2") (pinfunction "A_2") (pintype "passive"))
      (node (ref "Q6") (pin "1") (pinfunction "G_1") (pintype "passive"))
      (node (ref "R10") (pin "2") (pinfunction "2_2") (pintype "passive"))
      (node (ref "R13") (pin "2") (pinfunction "2_2") (pintype "passive"))
    )
    (net (code "30") (name "Net-(D7-C)") (class "Default")
      (node (ref "C9") (pin "1") (pinfunction "1_1") (pintype "passive"))
      (node (ref "D7") (pin "1") (pinfunction "C_1") (pintype "passive"))
      (node (ref "IC1") (pin "8") (pinfunction "VB_8") (pintype "passive"))
    )
    (net (code "31") (name "Net-(D8-C)") (class "Default")
      (node (ref "C12") (pin "1") (pinfunction "1_1") (pintype "passive"))
      (node (ref "D8") (pin "1") (pinfunction "C_1") (pintype "passive"))
      (node (ref "IC3") (pin "8") (pinfunction "VB_8") (pintype "passive"))
    )
    (net (code "32") (name "Net-(D9-C)") (class "Default")
      (node (ref "C15") (pin "1") (pinfunction "1_1") (pintype "passive"))
      (node (ref "D9") (pin "1") (pinfunction "C_1") (pintype "passive"))
      (node (ref "IC4") (pin "8") (pinfunction "VB_8") (pintype "passive"))
    )
    (net (code "33") (name "Net-(D10-C)") (class "Default")
      (node (ref "D10") (pin "1") (pinfunction "C_1") (pintype "passive"))
      (node (ref "R22") (pin "1") (pinfunction "1_1") (pintype "passive"))
    )
    (net (code "34") (name "Net-(IC2-PA0-WKUP)") (class "Default")
      (node (ref "IC2") (pin "10") (pinfunction "PA0-WKUP_10") (pintype "passive"))
      (node (ref "R19") (pin "1") (pinfunction "1_1") (pintype "passive"))
    )
    (net (code "35") (name "Net-(U1-ADJ)") (class "Default")
      (node (ref "C6") (pin "1") (pinfunction "1_1") (pintype "passive"))
      (node (ref "R11") (pin "2") (pinfunction "2_2") (pintype "passive"))
      (node (ref "R7") (pin "1") (pinfunction "1_1") (pintype "passive"))
      (node (ref "U1") (pin "1") (pinfunction "ADJ_1") (pintype "input"))
    )
    (net (code "36") (name "OSC8-1") (class "Default")
      (node (ref "C26") (pin "1") (pinfunction "1_1") (pintype "passive"))
      (node (ref "IC2") (pin "5") (pinfunction "PD0-OSC_IN_5") (pintype "passive"))
      (node (ref "Y2") (pin "2") (pinfunction "2_2") (pintype "passive"))
    )
    (net (code "37") (name "OSC8-2") (class "Default")
      (node (ref "C27") (pin "2") (pinfunction "2_2") (pintype "passive"))
      (node (ref "IC2") (pin "6") (pinfunction "PD1-OSC_OUT_6") (pintype "passive"))
      (node (ref "Y2") (pin "1") (pinfunction "1_1") (pintype "passive"))
    )
    (net (code "38") (name "OSC32-1") (class "Default")
      (node (ref "C23") (pin "1") (pinfunction "1_1") (pintype "passive"))
      (node (ref "IC2") (pin "3") (pinfunction "PC14-OSC32_IN_3") (pintype "passive"))
      (node (ref "Y1") (pin "3") (pinfunction "3_3") (pintype "passive"))
    )
    (net (code "39") (name "OSC32-2") (class "Default")
      (node (ref "C24") (pin "1") (pinfunction "1_1") (pintype "passive"))
      (node (ref "IC2") (pin "4") (pinfunction "PC15-OSC32_OUT_4") (pintype "passive"))
      (node (ref "Y1") (pin "1") (pinfunction "1_1") (pintype "passive"))
    )
    (net (code "40") (name "SWDCLK") (class "Default")
      (node (ref "IC2") (pin "37") (pinfunction "PA14_37") (pintype "passive"))
      (node (ref "P1") (pin "3") (pinfunction "3_3") (pintype "passive"))
    )
    (net (code "41") (name "SWDIO") (class "Default")
      (node (ref "IC2") (pin "34") (pinfunction "PA13_34") (pintype "passive"))
      (node (ref "P1") (pin "2") (pinfunction "2_2") (pintype "passive"))
    )
    (net (code "42") (name "Sigal") (class "Default")
      (node (ref "R19") (pin "2") (pinfunction "2_2") (pintype "passive"))
    )
    (net (code "43") (name "unconnected-(IC2-BOOT0-Pad44)") (class "Default")
      (node (ref "IC2") (pin "44") (pinfunction "BOOT0_44") (pintype "passive"))
    )
    (net (code "44") (name "unconnected-(IC2-PA4-Pad14)") (class "Default")
      (node (ref "IC2") (pin "14") (pinfunction "PA4_14") (pintype "passive"))
    )
    (net (code "45") (name "unconnected-(IC2-PA5-Pad15)") (class "Default")
      (node (ref "IC2") (pin "15") (pinfunction "PA5_15") (pintype "passive"))
    )
    (net (code "46") (name "unconnected-(IC2-PA6-Pad16)") (class "Default")
      (node (ref "IC2") (pin "16") (pinfunction "PA6_16") (pintype "passive"))
    )
    (net (code "47") (name "unconnected-(IC2-PA7-Pad17)") (class "Default")
      (node (ref "IC2") (pin "17") (pinfunction "PA7_17") (pintype "passive"))
    )
    (net (code "48") (name "unconnected-(IC2-PA11-Pad32)") (class "Default")
      (node (ref "IC2") (pin "32") (pinfunction "PA11_32") (pintype "passive"))
    )
    (net (code "49") (name "unconnected-(IC2-PA12-Pad33)") (class "Default")
      (node (ref "IC2") (pin "33") (pinfunction "PA12_33") (pintype "passive"))
    )
    (net (code "50") (name "unconnected-(IC2-PA15-Pad38)") (class "Default")
      (node (ref "IC2") (pin "38") (pinfunction "PA15_38") (pintype "passive"))
    )
    (net (code "51") (name "unconnected-(IC2-PB3-Pad39)") (class "Default")
      (node (ref "IC2") (pin "39") (pinfunction "PB3_39") (pintype "passive"))
    )
    (net (code "52") (name "unconnected-(IC2-PB4-Pad40)") (class "Default")
      (node (ref "IC2") (pin "40") (pinfunction "PB4_40") (pintype "passive"))
    )
    (net (code "53") (name "unconnected-(IC2-PB5-Pad41)") (class "Default")
      (node (ref "IC2") (pin "41") (pinfunction "PB5_41") (pintype "passive"))
    )
    (net (code "54") (name "unconnected-(IC2-PB6-Pad42)") (class "Default")
      (node (ref "IC2") (pin "42") (pinfunction "PB6_42") (pintype "passive"))
    )
    (net (code "55") (name "unconnected-(IC2-PB7-Pad43)") (class "Default")
      (node (ref "IC2") (pin "43") (pinfunction "PB7_43") (pintype "passive"))
    )
    (net (code "56") (name "unconnected-(IC2-PB8-Pad45)") (class "Default")
      (node (ref "IC2") (pin "45") (pinfunction "PB8_45") (pintype "passive"))
    )
    (net (code "57") (name "unconnected-(IC2-PB9-Pad46)") (class "Default")
      (node (ref "IC2") (pin "46") (pinfunction "PB9_46") (pintype "passive"))
    )
    (net (code "58") (name "unconnected-(IC2-PB10-Pad21)") (class "Default")
      (node (ref "IC2") (pin "21") (pinfunction "PB10_21") (pintype "passive"))
    )
    (net (code "59") (name "unconnected-(IC2-PB11-Pad22)") (class "Default")
      (node (ref "IC2") (pin "22") (pinfunction "PB11_22") (pintype "passive"))
    )
    (net (code "60") (name "unconnected-(IC2-PB12-Pad25)") (class "Default")
      (node (ref "IC2") (pin "25") (pinfunction "PB12_25") (pintype "passive"))
    )
    (net (code "61") (name "unconnected-(IC2-PB13-Pad26)") (class "Default")
      (node (ref "IC2") (pin "26") (pinfunction "PB13_26") (pintype "passive"))
    )
    (net (code "62") (name "unconnected-(IC2-PB14-Pad27)") (class "Default")
      (node (ref "IC2") (pin "27") (pinfunction "PB14_27") (pintype "passive"))
    )
    (net (code "63") (name "unconnected-(IC2-PB15-Pad28)") (class "Default")
      (node (ref "IC2") (pin "28") (pinfunction "PB15_28") (pintype "passive"))
    )
  )
)
